# Mosfets.net
KiCad netlist of a schematic drawn in Altium Designer
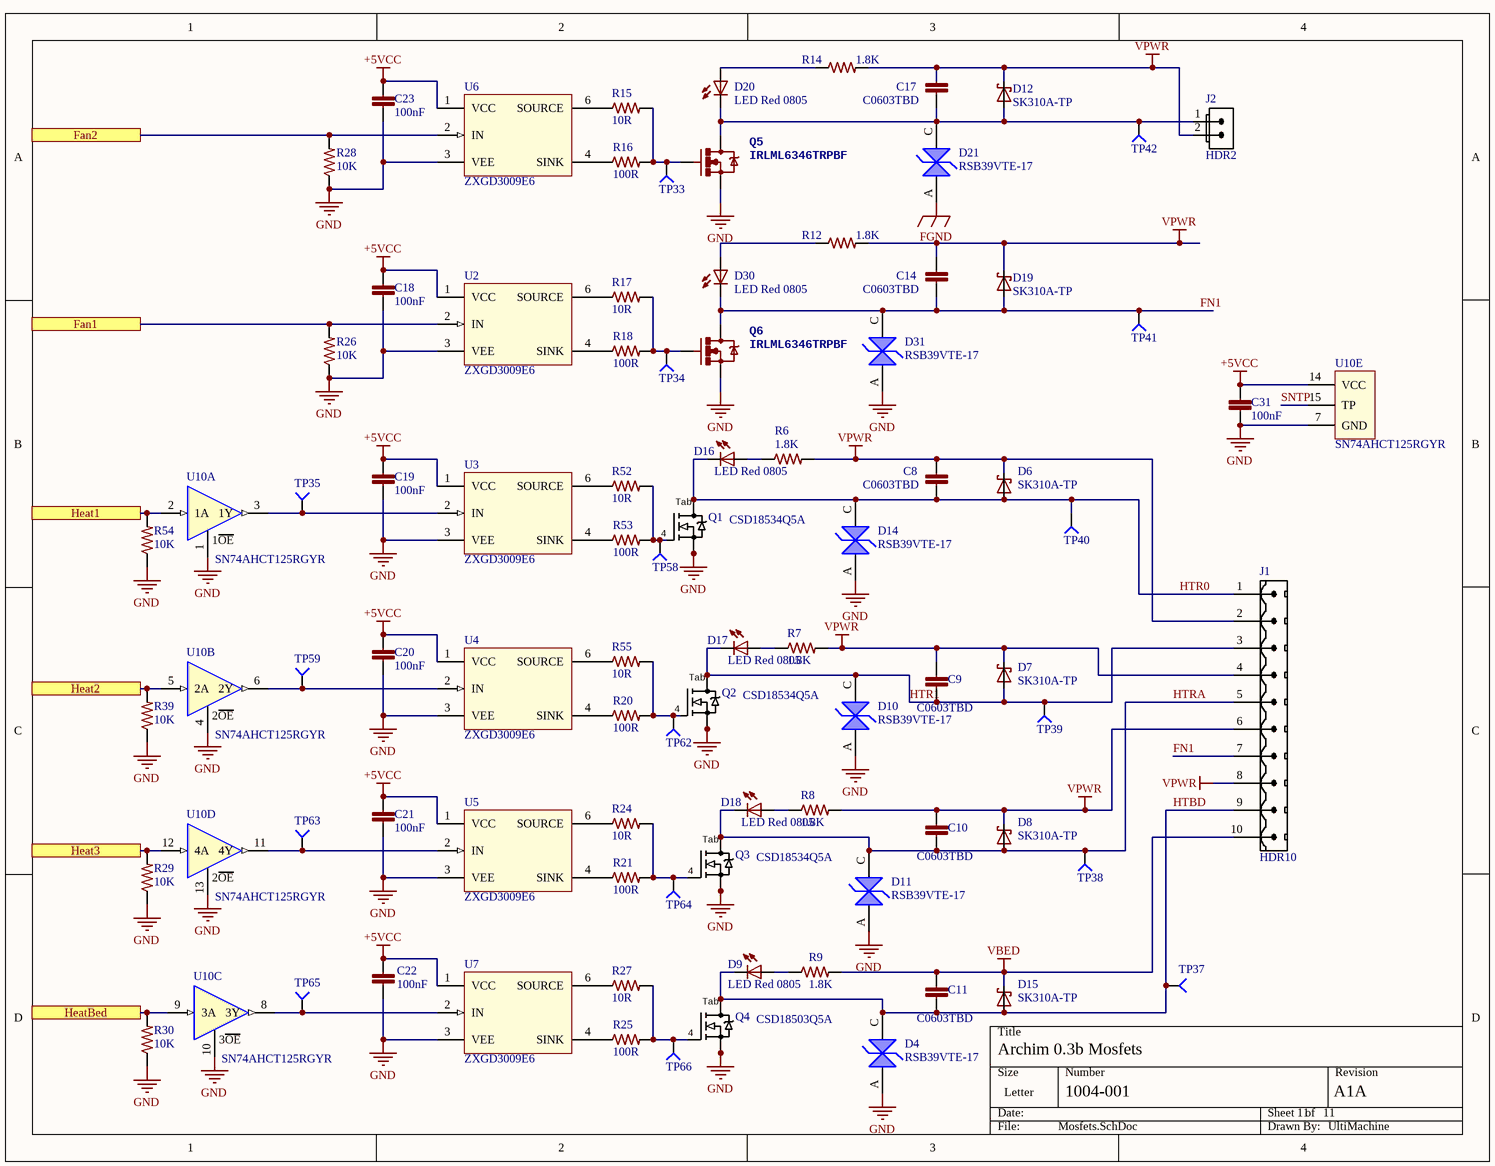
[diagram p0: Mosfets.SchDoc]

(export (version "E")
  (design (tool "Eeschema 10.0.6"))
  (components
    (comp (ref "C8")
      (value "C0603TBD")
      (footprint "C0603")
      (description "Capacitor Non Polarized")
      (libsource (lib "3Delight") (part "C0603TBD"))
    )
    (comp (ref "C9")
      (value "C0603TBD")
      (footprint "C0603")
      (description "Capacitor Non Polarized")
      (libsource (lib "3Delight") (part "C0603TBD"))
    )
    (comp (ref "C10")
      (value "C0603TBD")
      (footprint "C0603")
      (description "Capacitor Non Polarized")
      (libsource (lib "3Delight") (part "C0603TBD"))
    )
    (comp (ref "C11")
      (value "C0603TBD")
      (footprint "C0603")
      (description "Capacitor Non Polarized")
      (libsource (lib "3Delight") (part "C0603TBD"))
    )
    (comp (ref "C14")
      (value "C0603TBD")
      (footprint "C0603")
      (description "Capacitor Non Polarized")
      (libsource (lib "3Delight") (part "C0603TBD"))
    )
    (comp (ref "C17")
      (value "C0603TBD")
      (footprint "C0603")
      (description "Capacitor Non Polarized")
      (libsource (lib "3Delight") (part "C0603TBD"))
    )
    (comp (ref "C18")
      (value "100nF")
      (footprint "C0402")
      (description "CAP CER 0402 100nF 16V 10% X7R")
      (fields (field (name "MANUFACTURER") "Murata") (field (name "PART") "0.1uF 16V X7R 0402"))
      (libsource (lib "3Delight") (part "GRM155R71C104KA88D"))
    )
    (comp (ref "C19")
      (value "100nF")
      (footprint "C0402")
      (description "CAP CER 0402 100nF 16V 10% X7R")
      (fields (field (name "MANUFACTURER") "Murata") (field (name "PART") "0.1uF 16V X7R 0402"))
      (libsource (lib "3Delight") (part "GRM155R71C104KA88D"))
    )
    (comp (ref "C20")
      (value "100nF")
      (footprint "C0402")
      (description "CAP CER 0402 100nF 16V 10% X7R")
      (fields (field (name "MANUFACTURER") "Murata") (field (name "PART") "0.1uF 16V X7R 0402"))
      (libsource (lib "3Delight") (part "GRM155R71C104KA88D"))
    )
    (comp (ref "C21")
      (value "100nF")
      (footprint "C0402")
      (description "CAP CER 0402 100nF 16V 10% X7R")
      (fields (field (name "MANUFACTURER") "Murata") (field (name "PART") "0.1uF 16V X7R 0402"))
      (libsource (lib "3Delight") (part "GRM155R71C104KA88D"))
    )
    (comp (ref "C22")
      (value "100nF")
      (footprint "C0402")
      (description "CAP CER 0402 100nF 16V 10% X7R")
      (fields (field (name "MANUFACTURER") "Murata") (field (name "PART") "0.1uF 16V X7R 0402"))
      (libsource (lib "") (part "GRM155R71C104KA88D_1"))
    )
    (comp (ref "C23")
      (value "100nF")
      (footprint "C0402")
      (description "CAP CER 0402 100nF 16V 10% X7R")
      (fields (field (name "MANUFACTURER") "Murata") (field (name "PART") "0.1uF 16V X7R 0402"))
      (libsource (lib "3Delight") (part "GRM155R71C104KA88D"))
    )
    (comp (ref "C31")
      (value "100nF")
      (footprint "C0402")
      (description "CAP CER 0402 100nF 16V 10% X7R")
      (fields (field (name "MANUFACTURER") "Murata") (field (name "PART") "0.1uF 16V X7R 0402"))
      (libsource (lib "3Delight") (part "GRM155R71C104KA88D"))
    )
    (comp (ref "D4")
      (value "RSB39VTE-17")
      (footprint "SOD323-R")
      (description "DIODE TVS")
      (fields (field (name "MANUFACTURER") "Rohm") (field (name "PART") "TVS DIODE 30VWM SOD323"))
      (libsource (lib "3Delight") (part "RSB39VTE-17"))
    )
    (comp (ref "D6")
      (value "SK310A-TP")
      (footprint "SMA-SM")
      (description "DIODE Schottky 3A SMA")
      (fields (field (name "MANUFACTURER") "MCC") (field (name "PART") "Schottky Diode 100V 3A"))
      (libsource (lib "Archim_0.4") (part "SK310A"))
    )
    (comp (ref "D7")
      (value "SK310A-TP")
      (footprint "SMA-SM")
      (description "DIODE Schottky 3A SMA")
      (fields (field (name "MANUFACTURER") "MCC") (field (name "PART") "Schottky Diode 100V 3A"))
      (libsource (lib "Archim_0.4") (part "SK310A"))
    )
    (comp (ref "D8")
      (value "SK310A-TP")
      (footprint "SMA-SM")
      (description "DIODE Schottky 3A SMA")
      (fields (field (name "MANUFACTURER") "MCC") (field (name "PART") "Schottky Diode 100V 3A"))
      (libsource (lib "Archim_0.4") (part "SK310A"))
    )
    (comp (ref "D9")
      (value "Red")
      (footprint "LED2012120")
      (description "LED 0805 Red")
      (fields
        (field (name "MANUFACTURER") "Dialight")
        (field (name "PART") "LED Red 0805")
        (field (name "TOLERANCE") "-NA-")
      )
      (libsource (lib "3Delight") (part "5988110107F"))
    )
    (comp (ref "D10")
      (value "RSB39VTE-17")
      (footprint "SOD323-R")
      (description "DIODE TVS")
      (fields (field (name "MANUFACTURER") "Rohm") (field (name "PART") "TVS DIODE 30VWM SOD323"))
      (libsource (lib "3Delight") (part "RSB39VTE-17"))
    )
    (comp (ref "D11")
      (value "RSB39VTE-17")
      (footprint "SOD323-R")
      (description "DIODE TVS")
      (fields (field (name "MANUFACTURER") "Rohm") (field (name "PART") "TVS DIODE 30VWM SOD323"))
      (libsource (lib "3Delight") (part "RSB39VTE-17"))
    )
    (comp (ref "D12")
      (value "SK310A-TP")
      (footprint "SMA-SM")
      (description "DIODE Schottky 3A SMA")
      (fields (field (name "MANUFACTURER") "MCC") (field (name "PART") "Schottky Diode 100V 3A"))
      (libsource (lib "Archim_0.4") (part "SK310A"))
    )
    (comp (ref "D14")
      (value "RSB39VTE-17")
      (footprint "SOD323-R")
      (description "DIODE TVS")
      (fields (field (name "MANUFACTURER") "Rohm") (field (name "PART") "TVS DIODE 30VWM SOD323"))
      (libsource (lib "3Delight") (part "RSB39VTE-17"))
    )
    (comp (ref "D15")
      (value "SK310A-TP")
      (footprint "SMA-SM")
      (description "DIODE Schottky 3A SMA")
      (fields (field (name "MANUFACTURER") "MCC") (field (name "PART") "Schottky Diode 100V 3A"))
      (libsource (lib "Archim_0.4") (part "SK310A"))
    )
    (comp (ref "D16")
      (value "Red")
      (footprint "LED2012120")
      (description "LED 0805 Red")
      (fields
        (field (name "MANUFACTURER") "Dialight")
        (field (name "PART") "LED Red 0805")
        (field (name "TOLERANCE") "-NA-")
      )
      (libsource (lib "3Delight") (part "5988110107F"))
    )
    (comp (ref "D17")
      (value "Red")
      (footprint "LED2012120")
      (description "LED 0805 Red")
      (fields
        (field (name "MANUFACTURER") "Dialight")
        (field (name "PART") "LED Red 0805")
        (field (name "TOLERANCE") "-NA-")
      )
      (libsource (lib "3Delight") (part "5988110107F"))
    )
    (comp (ref "D18")
      (value "Red")
      (footprint "LED2012120")
      (description "LED 0805 Red")
      (fields
        (field (name "MANUFACTURER") "Dialight")
        (field (name "PART") "LED Red 0805")
        (field (name "TOLERANCE") "-NA-")
      )
      (libsource (lib "3Delight") (part "5988110107F"))
    )
    (comp (ref "D19")
      (value "SK310A-TP")
      (footprint "SMA-SM")
      (description "DIODE Schottky 3A SMA")
      (fields (field (name "MANUFACTURER") "MCC") (field (name "PART") "Schottky Diode 100V 3A"))
      (libsource (lib "Archim_0.4") (part "SK310A"))
    )
    (comp (ref "D20")
      (value "Red")
      (footprint "LED2012120")
      (description "LED 0805 Red")
      (fields
        (field (name "MANUFACTURER") "Dialight")
        (field (name "PART") "LED Red 0805")
        (field (name "TOLERANCE") "-NA-")
      )
      (libsource (lib "3Delight") (part "5988110107F"))
    )
    (comp (ref "D21")
      (value "RSB39VTE-17")
      (footprint "SOD323-R")
      (description "DIODE TVS")
      (fields (field (name "MANUFACTURER") "Rohm") (field (name "PART") "TVS DIODE 30VWM SOD323"))
      (libsource (lib "3Delight") (part "RSB39VTE-17"))
    )
    (comp (ref "D30")
      (value "Red")
      (footprint "LED2012120")
      (description "LED 0805 Red")
      (fields
        (field (name "MANUFACTURER") "Dialight")
        (field (name "PART") "LED Red 0805")
        (field (name "TOLERANCE") "-NA-")
      )
      (libsource (lib "3Delight") (part "5988110107F"))
    )
    (comp (ref "D31")
      (value "RSB39VTE-17")
      (footprint "SOD323-R")
      (description "DIODE TVS")
      (fields (field (name "MANUFACTURER") "Rohm") (field (name "PART") "TVS DIODE 30VWM SOD323"))
      (libsource (lib "3Delight") (part "RSB39VTE-17"))
    )
    (comp (ref "J1")
      (value "HDR10")
      (footprint "MSTBV10")
      (description "MSBTV10 10 port connector same as RAMBo")
      (fields
        (field (name "MANUFACTURER") "Molex")
        (field (name "PART") "CONN TERM BLOCK HDR 10POS VERT 5.08MM")
      )
      (libsource (lib "Archim_0.4") (part "CONN 10POS 0.2{dblquote} VERT SHRD"))
    )
    (comp (ref "J2")
      (value "HDR2")
      (footprint "70543-01 PIN-IN-PASTE")
      (description "Connector 2pos - Pin in Paste")
      (fields (field (name "MANUFACTURER") "Molex") (field (name "PART") "2 Pin Conn"))
      (libsource (lib "Connectors") (part "CONN 2PIN VERT 0.1{dblquote} SHRD LOCKING PIP"))
    )
    (comp (ref "Q1")
      (value "CSD18534Q5A")
      (footprint "SOT669_Universal")
      (description "MOSFET N-CH 40V 100A 8VSON")
      (fields (field (name "MANUFACTURER") "TI"))
      (libsource (lib "Transistors") (part "CSD18534Q5A"))
    )
    (comp (ref "Q2")
      (value "CSD18534Q5A")
      (footprint "SOT669_Universal")
      (description "MOSFET N-CH 40V 100A 8VSON")
      (fields (field (name "MANUFACTURER") "TI"))
      (libsource (lib "Transistors") (part "CSD18534Q5A"))
    )
    (comp (ref "Q3")
      (value "CSD18534Q5A")
      (footprint "SOT669_Universal")
      (description "MOSFET N-CH 40V 100A 8VSON")
      (fields (field (name "MANUFACTURER") "TI"))
      (libsource (lib "Transistors") (part "CSD18534Q5A"))
    )
    (comp (ref "Q4")
      (value "CSD18503Q5A")
      (footprint "SOT669_Universal")
      (description "MOSFET N-CH 40V 100A 8VSON")
      (fields (field (name "MANUFACTURER") "TI"))
      (libsource (lib "Transistors") (part "CSD18503Q5A"))
    )
    (comp (ref "Q5")
      (value "IRLML6346TRPBF")
      (footprint "SOT23-3")
      (description "Mosfet N-Channel 30V 3.4A 63mOhm")
      (fields (field (name "MANUFACTURER") "Infineon") (field (name "PART") "MOSFET N-Chan 30V 3.4A"))
      (libsource (lib "3Delight") (part "IRLML6346TRPBF"))
    )
    (comp (ref "Q6")
      (value "IRLML6346TRPBF")
      (footprint "SOT23-3")
      (description "Mosfet N-Channel 30V 3.4A 63mOhm")
      (fields (field (name "MANUFACTURER") "Infineon") (field (name "PART") "MOSFET N-Chan 30V 3.4A"))
      (libsource (lib "3Delight") (part "IRLML6346TRPBF"))
    )
    (comp (ref "R6")
      (value "1.8K")
      (footprint "R0603")
      (description "RES 0603 1.8K 100mW 5%")
      (fields (field (name "MANUFACTURER") "Yageo") (field (name "PART") "1.8k 5% 0603"))
      (libsource (lib "3Delight") (part "RC0603JR-071K8L"))
    )
    (comp (ref "R7")
      (value "1.8K")
      (footprint "R0603")
      (description "RES 0603 1.8K 100mW 5%")
      (fields (field (name "MANUFACTURER") "Yageo") (field (name "PART") "1.8k 5% 0603"))
      (libsource (lib "3Delight") (part "RC0603JR-071K8L"))
    )
    (comp (ref "R8")
      (value "1.8K")
      (footprint "R0603")
      (description "RES 0603 1.8K 100mW 5%")
      (fields (field (name "MANUFACTURER") "Yageo") (field (name "PART") "1.8k 5% 0603"))
      (libsource (lib "3Delight") (part "RC0603JR-071K8L"))
    )
    (comp (ref "R9")
      (value "1.8K")
      (footprint "R0603")
      (description "RES 0603 1.8K 100mW 5%")
      (fields (field (name "MANUFACTURER") "Yageo") (field (name "PART") "1.8k 5% 0603"))
      (libsource (lib "3Delight") (part "RC0603JR-071K8L"))
    )
    (comp (ref "R12")
      (value "1.8K")
      (footprint "R0603")
      (description "RES 0603 1.8K 100mW 5%")
      (fields (field (name "MANUFACTURER") "Yageo") (field (name "PART") "1.8k 5% 0603"))
      (libsource (lib "3Delight") (part "RC0603JR-071K8L"))
    )
    (comp (ref "R14")
      (value "1.8K")
      (footprint "R0603")
      (description "RES 0603 1.8K 100mW 5%")
      (fields (field (name "MANUFACTURER") "Yageo") (field (name "PART") "1.8k 5% 0603"))
      (libsource (lib "3Delight") (part "RC0603JR-071K8L"))
    )
    (comp (ref "R15")
      (value "10R")
      (footprint "R0402")
      (description "RES SMD 10 OHM 1% 1/16W 0402")
      (fields (field (name "MANUFACTURER") "Yageo") (field (name "TOLERANCE") "1%"))
      (libsource (lib "3Delight") (part "RC0402FR-0710RL"))
    )
    (comp (ref "R16")
      (value "100R")
      (footprint "R0402")
      (description "RES SMD 100 OHM 1% 1/16W 0402")
      (fields (field (name "MANUFACTURER") "Yageo") (field (name "PART") "100R 1% 0402"))
      (libsource (lib "Archim") (part "RES 100R 0402 1%"))
    )
    (comp (ref "R17")
      (value "10R")
      (footprint "R0402")
      (description "RES SMD 10 OHM 1% 1/16W 0402")
      (fields (field (name "MANUFACTURER") "Yageo") (field (name "TOLERANCE") "1%"))
      (libsource (lib "3Delight") (part "RC0402FR-0710RL"))
    )
    (comp (ref "R18")
      (value "100R")
      (footprint "R0402")
      (description "RES SMD 100 OHM 1% 1/16W 0402")
      (fields (field (name "MANUFACTURER") "Yageo") (field (name "PART") "100R 1% 0402"))
      (libsource (lib "Archim") (part "RES 100R 0402 1%"))
    )
    (comp (ref "R20")
      (value "100R")
      (footprint "R0402")
      (description "RES SMD 100 OHM 1% 1/16W 0402")
      (fields (field (name "MANUFACTURER") "Yageo") (field (name "PART") "100R 1% 0402"))
      (libsource (lib "Archim") (part "RES 100R 0402 1%"))
    )
    (comp (ref "R21")
      (value "100R")
      (footprint "R0402")
      (description "RES SMD 100 OHM 1% 1/16W 0402")
      (fields (field (name "MANUFACTURER") "Yageo") (field (name "PART") "100R 1% 0402"))
      (libsource (lib "Archim") (part "RES 100R 0402 1%"))
    )
    (comp (ref "R24")
      (value "10R")
      (footprint "R0402")
      (description "RES SMD 10 OHM 1% 1/16W 0402")
      (fields (field (name "MANUFACTURER") "Yageo") (field (name "TOLERANCE") "1%"))
      (libsource (lib "3Delight") (part "RC0402FR-0710RL"))
    )
    (comp (ref "R25")
      (value "100R")
      (footprint "R0402")
      (description "RES SMD 100 OHM 1% 1/16W 0402")
      (fields (field (name "MANUFACTURER") "Yageo") (field (name "PART") "100R 1% 0402"))
      (libsource (lib "Archim") (part "RES 100R 0402 1%"))
    )
    (comp (ref "R26")
      (value "10K")
      (footprint "R0402")
      (description "RES SMD 10K OHM 1% 1/16W 0402")
      (fields (field (name "MANUFACTURER") "Yageo") (field (name "PART") "10k 1% 0402"))
      (libsource (lib "3Delight") (part "RC0402FR-0710KP"))
    )
    (comp (ref "R27")
      (value "10R")
      (footprint "R0402")
      (description "RES SMD 10 OHM 1% 1/16W 0402")
      (fields (field (name "MANUFACTURER") "Yageo") (field (name "TOLERANCE") "1%"))
      (libsource (lib "3Delight") (part "RC0402FR-0710RL"))
    )
    (comp (ref "R28")
      (value "10K")
      (footprint "R0402")
      (description "RES SMD 10K OHM 1% 1/16W 0402")
      (fields (field (name "MANUFACTURER") "Yageo") (field (name "PART") "10k 1% 0402"))
      (libsource (lib "3Delight") (part "RC0402FR-0710KP"))
    )
    (comp (ref "R29")
      (value "10K")
      (footprint "R0402")
      (description "RES SMD 10K OHM 1% 1/16W 0402")
      (fields (field (name "MANUFACTURER") "Yageo") (field (name "PART") "10k 1% 0402"))
      (libsource (lib "3Delight") (part "RC0402FR-0710KP"))
    )
    (comp (ref "R30")
      (value "10K")
      (footprint "R0402")
      (description "RES SMD 10K OHM 1% 1/16W 0402")
      (fields (field (name "MANUFACTURER") "Yageo") (field (name "PART") "10k 1% 0402"))
      (libsource (lib "3Delight") (part "RC0402FR-0710KP"))
    )
    (comp (ref "R39")
      (value "10K")
      (footprint "R0402")
      (description "RES SMD 10K OHM 1% 1/16W 0402")
      (fields (field (name "MANUFACTURER") "Yageo") (field (name "PART") "10k 1% 0402"))
      (libsource (lib "3Delight") (part "RC0402FR-0710KP"))
    )
    (comp (ref "R52")
      (value "10R")
      (footprint "R0402")
      (description "RES SMD 10 OHM 1% 1/16W 0402")
      (fields (field (name "MANUFACTURER") "Yageo") (field (name "TOLERANCE") "1%"))
      (libsource (lib "3Delight") (part "RC0402FR-0710RL"))
    )
    (comp (ref "R53")
      (value "100R")
      (footprint "R0402")
      (description "RES SMD 100 OHM 1% 1/16W 0402")
      (fields (field (name "MANUFACTURER") "Yageo") (field (name "PART") "100R 1% 0402"))
      (libsource (lib "Archim") (part "RES 100R 0402 1%"))
    )
    (comp (ref "R54")
      (value "10K")
      (footprint "R0402")
      (description "RES SMD 10K OHM 1% 1/16W 0402")
      (fields (field (name "MANUFACTURER") "Yageo") (field (name "PART") "10k 1% 0402"))
      (libsource (lib "3Delight") (part "RC0402FR-0710KP"))
    )
    (comp (ref "R55")
      (value "10R")
      (footprint "R0402")
      (description "RES SMD 10 OHM 1% 1/16W 0402")
      (fields (field (name "MANUFACTURER") "Yageo") (field (name "TOLERANCE") "1%"))
      (libsource (lib "3Delight") (part "RC0402FR-0710RL"))
    )
    (comp (ref "TP33")
      (value "TP4")
      (footprint "TP-2")
      (description "Socket")
      (libsource (lib "Archim") (part "Socket"))
    )
    (comp (ref "TP34")
      (value "TP4")
      (footprint "TP-2")
      (description "Socket")
      (libsource (lib "Archim") (part "Socket"))
    )
    (comp (ref "TP35")
      (value "TP4")
      (footprint "TP-2")
      (description "Socket")
      (libsource (lib "Archim") (part "Socket"))
    )
    (comp (ref "TP37")
      (value "TP4")
      (footprint "TP-2")
      (description "Socket")
      (libsource (lib "Archim") (part "Socket"))
    )
    (comp (ref "TP38")
      (value "TP4")
      (footprint "TP-2")
      (description "Socket")
      (libsource (lib "Archim") (part "Socket"))
    )
    (comp (ref "TP39")
      (value "TP4")
      (footprint "TP-2")
      (description "Socket")
      (libsource (lib "Archim") (part "Socket"))
    )
    (comp (ref "TP40")
      (value "TP4")
      (footprint "TP-2")
      (description "Socket")
      (libsource (lib "Archim") (part "Socket"))
    )
    (comp (ref "TP41")
      (value "TP4")
      (footprint "TP-2")
      (description "Socket")
      (libsource (lib "Archim") (part "Socket"))
    )
    (comp (ref "TP42")
      (value "TP4")
      (footprint "TP-2")
      (description "Socket")
      (libsource (lib "Archim") (part "Socket"))
    )
    (comp (ref "TP58")
      (value "TP4")
      (footprint "TP-2")
      (description "Socket")
      (libsource (lib "Archim") (part "Socket"))
    )
    (comp (ref "TP59")
      (value "TP4")
      (footprint "TP-2")
      (description "Socket")
      (libsource (lib "Archim") (part "Socket"))
    )
    (comp (ref "TP62")
      (value "TP4")
      (footprint "TP-2")
      (description "Socket")
      (libsource (lib "Archim") (part "Socket"))
    )
    (comp (ref "TP63")
      (value "TP4")
      (footprint "TP-2")
      (description "Socket")
      (libsource (lib "Archim") (part "Socket"))
    )
    (comp (ref "TP64")
      (value "TP4")
      (footprint "TP-2")
      (description "Socket")
      (libsource (lib "Archim") (part "Socket"))
    )
    (comp (ref "TP65")
      (value "TP4")
      (footprint "TP-2")
      (description "Socket")
      (libsource (lib "Archim") (part "Socket"))
    )
    (comp (ref "TP66")
      (value "TP4")
      (footprint "TP-2")
      (description "Socket")
      (libsource (lib "Archim") (part "Socket"))
    )
    (comp (ref "U2")
      (value "ZXGD3009E6")
      (footprint "SOT26P285X140-6L")
      (description "MOSFET DRVR 3A 1-OUT High Speed Non-Inv6-Pin SOT-26 T/R")
      (fields
        (field (name "MANUFACTURER") "Diodes Incorporated")
        (field (name "PART") "IC GATE DRVR IGBT/MOSFET SOT23-6")
      )
      (libsource (lib "3Delight") (part "ZXGD3009E6"))
    )
    (comp (ref "U3")
      (value "ZXGD3009E6")
      (footprint "SOT26P285X140-6L")
      (description "MOSFET DRVR 3A 1-OUT High Speed Non-Inv6-Pin SOT-26 T/R")
      (fields
        (field (name "MANUFACTURER") "Diodes Incorporated")
        (field (name "PART") "IC GATE DRVR IGBT/MOSFET SOT23-6")
      )
      (libsource (lib "3Delight") (part "ZXGD3009E6"))
    )
    (comp (ref "U4")
      (value "ZXGD3009E6")
      (footprint "SOT26P285X140-6L")
      (description "MOSFET DRVR 3A 1-OUT High Speed Non-Inv6-Pin SOT-26 T/R")
      (fields
        (field (name "MANUFACTURER") "Diodes Incorporated")
        (field (name "PART") "IC GATE DRVR IGBT/MOSFET SOT23-6")
      )
      (libsource (lib "3Delight") (part "ZXGD3009E6"))
    )
    (comp (ref "U5")
      (value "ZXGD3009E6")
      (footprint "SOT26P285X140-6L")
      (description "MOSFET DRVR 3A 1-OUT High Speed Non-Inv6-Pin SOT-26 T/R")
      (fields
        (field (name "MANUFACTURER") "Diodes Incorporated")
        (field (name "PART") "IC GATE DRVR IGBT/MOSFET SOT23-6")
      )
      (libsource (lib "3Delight") (part "ZXGD3009E6"))
    )
    (comp (ref "U6")
      (value "ZXGD3009E6")
      (footprint "SOT26P285X140-6L")
      (description "MOSFET DRVR 3A 1-OUT High Speed Non-Inv6-Pin SOT-26 T/R")
      (fields
        (field (name "MANUFACTURER") "Diodes Incorporated")
        (field (name "PART") "IC GATE DRVR IGBT/MOSFET SOT23-6")
      )
      (libsource (lib "3Delight") (part "ZXGD3009E6"))
    )
    (comp (ref "U7")
      (value "ZXGD3009E6")
      (footprint "SOT26P285X140-6L")
      (description "MOSFET DRVR 3A 1-OUT High Speed Non-Inv6-Pin SOT-26 T/R")
      (fields
        (field (name "MANUFACTURER") "Diodes Incorporated")
        (field (name "PART") "IC GATE DRVR IGBT/MOSFET SOT23-6")
      )
      (libsource (lib "3Delight") (part "ZXGD3009E6"))
    )
    (comp (ref "U10")
      (value "SN74AHCT125RGYR")
      (footprint "QFN50P350X350X100_RGY_S-PVQFN-N14")
      (description "Quadruple Bus Buffer Gates With 3-State Outputs 14-VQFN -40 to 125")
      (fields
        (field (name "MANUFACTURER") "Texas Instruments")
        (field (name "PART") "IC BUS BUFFER TRI-ST QD 14VQFN")
      )
      (libsource (lib "3Delight") (part "SN74AHCT125"))
    )
  )
  (nets
    (net (code "1") (name "+5VCC") (class "Default")
      (node (ref "C18") (pin "2") (pinfunction "2_2") (pintype "passive"))
      (node (ref "C19") (pin "2") (pinfunction "2_2") (pintype "passive"))
      (node (ref "C20") (pin "2") (pinfunction "2_2") (pintype "passive"))
      (node (ref "C21") (pin "2") (pinfunction "2_2") (pintype "passive"))
      (node (ref "C22") (pin "1") (pinfunction "1_1") (pintype "passive"))
      (node (ref "C23") (pin "2") (pinfunction "2_2") (pintype "passive"))
      (node (ref "C31") (pin "2") (pinfunction "2_2") (pintype "passive"))
      (node (ref "U10") (pin "14") (pinfunction "VCC_14") (pintype "power_in"))
      (node (ref "U2") (pin "1") (pinfunction "VCC_1") (pintype "power_in"))
      (node (ref "U3") (pin "1") (pinfunction "VCC_1") (pintype "power_in"))
      (node (ref "U4") (pin "1") (pinfunction "VCC_1") (pintype "power_in"))
      (node (ref "U5") (pin "1") (pinfunction "VCC_1") (pintype "power_in"))
      (node (ref "U6") (pin "1") (pinfunction "VCC_1") (pintype "power_in"))
      (node (ref "U7") (pin "1") (pinfunction "VCC_1") (pintype "power_in"))
    )
    (net (code "2") (name "/FN1") (class "Default")
      (node (ref "C14") (pin "2") (pinfunction "2_2") (pintype "passive"))
      (node (ref "D19") (pin "A") (pinfunction "A_A") (pintype "passive"))
      (node (ref "D30") (pin "C") (pinfunction "C_C") (pintype "passive"))
      (node (ref "D31") (pin "C") (pinfunction "C_C") (pintype "power_in"))
      (node (ref "J1") (pin "7") (pinfunction "7_7") (pintype "passive"))
      (node (ref "Q6") (pin "3") (pinfunction "D_3") (pintype "passive"))
      (node (ref "TP41") (pin "1") (pinfunction "1_1") (pintype "passive"))
    )
    (net (code "3") (name "/Fan1") (class "Default")
      (node (ref "R26") (pin "2") (pinfunction "2_2") (pintype "passive"))
      (node (ref "U2") (pin "2") (pinfunction "IN_2") (pintype "input"))
    )
    (net (code "4") (name "/Fan2") (class "Default")
      (node (ref "R28") (pin "2") (pinfunction "2_2") (pintype "passive"))
      (node (ref "U6") (pin "2") (pinfunction "IN_2") (pintype "input"))
    )
    (net (code "5") (name "/HTBD") (class "Default")
      (node (ref "C11") (pin "2") (pinfunction "2_2") (pintype "passive"))
      (node (ref "D15") (pin "A") (pinfunction "A_A") (pintype "passive"))
      (node (ref "D4") (pin "C") (pinfunction "C_C") (pintype "power_in"))
      (node (ref "D9") (pin "C") (pinfunction "C_C") (pintype "passive"))
      (node (ref "J1") (pin "9") (pinfunction "9_9") (pintype "passive"))
      (node (ref "Q4") (pin "TAB") (pinfunction "D_TAB") (pintype "passive"))
      (node (ref "TP37") (pin "1") (pinfunction "1_1") (pintype "passive"))
    )
    (net (code "6") (name "/HTR0") (class "Default")
      (node (ref "C8") (pin "2") (pinfunction "2_2") (pintype "passive"))
      (node (ref "D14") (pin "C") (pinfunction "C_C") (pintype "power_in"))
      (node (ref "D16") (pin "C") (pinfunction "C_C") (pintype "passive"))
      (node (ref "D6") (pin "A") (pinfunction "A_A") (pintype "passive"))
      (node (ref "J1") (pin "1") (pinfunction "1_1") (pintype "passive"))
      (node (ref "Q1") (pin "TAB") (pinfunction "D_TAB") (pintype "passive"))
      (node (ref "TP40") (pin "1") (pinfunction "1_1") (pintype "passive"))
    )
    (net (code "7") (name "/HTR1") (class "Default")
      (node (ref "C9") (pin "2") (pinfunction "2_2") (pintype "passive"))
      (node (ref "D10") (pin "C") (pinfunction "C_C") (pintype "power_in"))
      (node (ref "D17") (pin "C") (pinfunction "C_C") (pintype "passive"))
      (node (ref "D7") (pin "A") (pinfunction "A_A") (pintype "passive"))
      (node (ref "J1") (pin "3") (pinfunction "3_3") (pintype "passive"))
      (node (ref "Q2") (pin "TAB") (pinfunction "D_TAB") (pintype "passive"))
      (node (ref "TP39") (pin "1") (pinfunction "1_1") (pintype "passive"))
    )
    (net (code "8") (name "/HTRA") (class "Default")
      (node (ref "C10") (pin "2") (pinfunction "2_2") (pintype "passive"))
      (node (ref "D11") (pin "C") (pinfunction "C_C") (pintype "power_in"))
      (node (ref "D18") (pin "C") (pinfunction "C_C") (pintype "passive"))
      (node (ref "D8") (pin "A") (pinfunction "A_A") (pintype "passive"))
      (node (ref "J1") (pin "5") (pinfunction "5_5") (pintype "passive"))
      (node (ref "Q3") (pin "TAB") (pinfunction "D_TAB") (pintype "passive"))
      (node (ref "TP38") (pin "1") (pinfunction "1_1") (pintype "passive"))
    )
    (net (code "9") (name "/Heat1") (class "Default")
      (node (ref "R54") (pin "2") (pinfunction "2_2") (pintype "passive"))
      (node (ref "U10") (pin "2") (pinfunction "1A_2") (pintype "input"))
    )
    (net (code "10") (name "/Heat2") (class "Default")
      (node (ref "R39") (pin "2") (pinfunction "2_2") (pintype "passive"))
      (node (ref "U10") (pin "5") (pinfunction "2A_5") (pintype "input"))
    )
    (net (code "11") (name "/Heat3") (class "Default")
      (node (ref "R29") (pin "2") (pinfunction "2_2") (pintype "passive"))
      (node (ref "U10") (pin "12") (pinfunction "4A_12") (pintype "input"))
    )
    (net (code "12") (name "/HeatBed") (class "Default")
      (node (ref "R30") (pin "2") (pinfunction "2_2") (pintype "passive"))
      (node (ref "U10") (pin "9") (pinfunction "3A_9") (pintype "input"))
    )
    (net (code "13") (name "/SNTP") (class "Default")
      (node (ref "U10") (pin "15") (pinfunction "TP_15") (pintype "power_in"))
    )
    (net (code "14") (name "FGND") (class "Default")
      (node (ref "D21") (pin "A") (pinfunction "A_A") (pintype "power_in"))
    )
    (net (code "15") (name "GND") (class "Default")
      (node (ref "C18") (pin "1") (pinfunction "1_1") (pintype "passive"))
      (node (ref "C19") (pin "1") (pinfunction "1_1") (pintype "passive"))
      (node (ref "C20") (pin "1") (pinfunction "1_1") (pintype "passive"))
      (node (ref "C21") (pin "1") (pinfunction "1_1") (pintype "passive"))
      (node (ref "C22") (pin "2") (pinfunction "2_2") (pintype "passive"))
      (node (ref "C23") (pin "1") (pinfunction "1_1") (pintype "passive"))
      (node (ref "C31") (pin "1") (pinfunction "1_1") (pintype "passive"))
      (node (ref "D10") (pin "A") (pinfunction "A_A") (pintype "power_in"))
      (node (ref "D11") (pin "A") (pinfunction "A_A") (pintype "power_in"))
      (node (ref "D14") (pin "A") (pinfunction "A_A") (pintype "power_in"))
      (node (ref "D31") (pin "A") (pinfunction "A_A") (pintype "power_in"))
      (node (ref "D4") (pin "A") (pinfunction "A_A") (pintype "power_in"))
      (node (ref "Q1") (pin "1") (pinfunction "S_1") (pintype "passive"))
      (node (ref "Q1") (pin "2") (pinfunction "S_2") (pintype "passive"))
      (node (ref "Q1") (pin "3") (pinfunction "S_3") (pintype "passive"))
      (node (ref "Q2") (pin "1") (pinfunction "S_1") (pintype "passive"))
      (node (ref "Q2") (pin "2") (pinfunction "S_2") (pintype "passive"))
      (node (ref "Q2") (pin "3") (pinfunction "S_3") (pintype "passive"))
      (node (ref "Q3") (pin "1") (pinfunction "S_1") (pintype "passive"))
      (node (ref "Q3") (pin "2") (pinfunction "S_2") (pintype "passive"))
      (node (ref "Q3") (pin "3") (pinfunction "S_3") (pintype "passive"))
      (node (ref "Q4") (pin "1") (pinfunction "S_1") (pintype "passive"))
      (node (ref "Q4") (pin "2") (pinfunction "S_2") (pintype "passive"))
      (node (ref "Q4") (pin "3") (pinfunction "S_3") (pintype "passive"))
      (node (ref "Q5") (pin "2") (pinfunction "S_2") (pintype "passive"))
      (node (ref "Q6") (pin "2") (pinfunction "S_2") (pintype "passive"))
      (node (ref "R26") (pin "1") (pinfunction "1_1") (pintype "passive"))
      (node (ref "R28") (pin "1") (pinfunction "1_1") (pintype "passive"))
      (node (ref "R29") (pin "1") (pinfunction "1_1") (pintype "passive"))
      (node (ref "R30") (pin "1") (pinfunction "1_1") (pintype "passive"))
      (node (ref "R39") (pin "1") (pinfunction "1_1") (pintype "passive"))
      (node (ref "R54") (pin "1") (pinfunction "1_1") (pintype "passive"))
      (node (ref "U10") (pin "1") (pinfunction "1OE_1") (pintype "power_in"))
      (node (ref "U10") (pin "10") (pinfunction "3OE_10") (pintype "power_in"))
      (node (ref "U10") (pin "13") (pinfunction "4OE_13") (pintype "power_in"))
      (node (ref "U10") (pin "4") (pinfunction "2OE_4") (pintype "power_in"))
      (node (ref "U10") (pin "7") (pinfunction "GND_7") (pintype "power_in"))
      (node (ref "U2") (pin "3") (pinfunction "VEE_3") (pintype "power_in"))
      (node (ref "U3") (pin "3") (pinfunction "VEE_3") (pintype "power_in"))
      (node (ref "U4") (pin "3") (pinfunction "VEE_3") (pintype "power_in"))
      (node (ref "U5") (pin "3") (pinfunction "VEE_3") (pintype "power_in"))
      (node (ref "U6") (pin "3") (pinfunction "VEE_3") (pintype "power_in"))
      (node (ref "U7") (pin "3") (pinfunction "VEE_3") (pintype "power_in"))
    )
    (net (code "16") (name "Net-(D9-PadA)") (class "Default")
      (node (ref "D9") (pin "A") (pinfunction "A_A") (pintype "passive"))
      (node (ref "R9") (pin "1") (pinfunction "1_1") (pintype "passive"))
    )
    (net (code "17") (name "Net-(D16-PadA)") (class "Default")
      (node (ref "D16") (pin "A") (pinfunction "A_A") (pintype "passive"))
      (node (ref "R6") (pin "1") (pinfunction "1_1") (pintype "passive"))
    )
    (net (code "18") (name "Net-(D17-PadA)") (class "Default")
      (node (ref "D17") (pin "A") (pinfunction "A_A") (pintype "passive"))
      (node (ref "R7") (pin "1") (pinfunction "1_1") (pintype "passive"))
    )
    (net (code "19") (name "Net-(D18-PadA)") (class "Default")
      (node (ref "D18") (pin "A") (pinfunction "A_A") (pintype "passive"))
      (node (ref "R8") (pin "1") (pinfunction "1_1") (pintype "passive"))
    )
    (net (code "20") (name "Net-(D20-PadA)") (class "Default")
      (node (ref "D20") (pin "A") (pinfunction "A_A") (pintype "passive"))
      (node (ref "R14") (pin "1") (pinfunction "1_1") (pintype "passive"))
    )
    (net (code "21") (name "Net-(D30-PadA)") (class "Default")
      (node (ref "D30") (pin "A") (pinfunction "A_A") (pintype "passive"))
      (node (ref "R12") (pin "1") (pinfunction "1_1") (pintype "passive"))
    )
    (net (code "22") (name "Net-(Q1-G)") (class "Default")
      (node (ref "Q1") (pin "4") (pinfunction "G_4") (pintype "passive"))
      (node (ref "R52") (pin "2") (pinfunction "2_2") (pintype "passive"))
      (node (ref "R53") (pin "2") (pinfunction "2_2") (pintype "passive"))
      (node (ref "TP58") (pin "1") (pinfunction "1_1") (pintype "passive"))
    )
    (net (code "23") (name "Net-(Q2-G)") (class "Default")
      (node (ref "Q2") (pin "4") (pinfunction "G_4") (pintype "passive"))
      (node (ref "R20") (pin "2") (pinfunction "2_2") (pintype "passive"))
      (node (ref "R55") (pin "2") (pinfunction "2_2") (pintype "passive"))
      (node (ref "TP62") (pin "1") (pinfunction "1_1") (pintype "passive"))
    )
    (net (code "24") (name "Net-(Q3-G)") (class "Default")
      (node (ref "Q3") (pin "4") (pinfunction "G_4") (pintype "passive"))
      (node (ref "R21") (pin "2") (pinfunction "2_2") (pintype "passive"))
      (node (ref "R24") (pin "2") (pinfunction "2_2") (pintype "passive"))
      (node (ref "TP64") (pin "1") (pinfunction "1_1") (pintype "passive"))
    )
    (net (code "25") (name "Net-(Q4-G)") (class "Default")
      (node (ref "Q4") (pin "4") (pinfunction "G_4") (pintype "passive"))
      (node (ref "R25") (pin "2") (pinfunction "2_2") (pintype "passive"))
      (node (ref "R27") (pin "2") (pinfunction "2_2") (pintype "passive"))
      (node (ref "TP66") (pin "1") (pinfunction "1_1") (pintype "passive"))
    )
    (net (code "26") (name "Net-(Q5-D)") (class "Default")
      (node (ref "C17") (pin "2") (pinfunction "2_2") (pintype "passive"))
      (node (ref "D12") (pin "A") (pinfunction "A_A") (pintype "passive"))
      (node (ref "D20") (pin "C") (pinfunction "C_C") (pintype "passive"))
      (node (ref "D21") (pin "C") (pinfunction "C_C") (pintype "power_in"))
      (node (ref "J2") (pin "1") (pinfunction "S_1") (pintype "passive"))
      (node (ref "Q5") (pin "3") (pinfunction "D_3") (pintype "passive"))
      (node (ref "TP42") (pin "1") (pinfunction "1_1") (pintype "passive"))
    )
    (net (code "27") (name "Net-(Q5-G)") (class "Default")
      (node (ref "Q5") (pin "1") (pinfunction "G_1") (pintype "passive"))
      (node (ref "R15") (pin "2") (pinfunction "2_2") (pintype "passive"))
      (node (ref "R16") (pin "2") (pinfunction "2_2") (pintype "passive"))
      (node (ref "TP33") (pin "1") (pinfunction "1_1") (pintype "passive"))
    )
    (net (code "28") (name "Net-(Q6-G)") (class "Default")
      (node (ref "Q6") (pin "1") (pinfunction "G_1") (pintype "passive"))
      (node (ref "R17") (pin "2") (pinfunction "2_2") (pintype "passive"))
      (node (ref "R18") (pin "2") (pinfunction "2_2") (pintype "passive"))
      (node (ref "TP34") (pin "1") (pinfunction "1_1") (pintype "passive"))
    )
    (net (code "29") (name "Net-(U2-SINK)") (class "Default")
      (node (ref "R18") (pin "1") (pinfunction "1_1") (pintype "passive"))
      (node (ref "U2") (pin "4") (pinfunction "SINK_4") (pintype "power_in"))
    )
    (net (code "30") (name "Net-(U2-SOURCE)") (class "Default")
      (node (ref "R17") (pin "1") (pinfunction "1_1") (pintype "passive"))
      (node (ref "U2") (pin "6") (pinfunction "SOURCE_6") (pintype "power_in"))
    )
    (net (code "31") (name "Net-(U3-SINK)") (class "Default")
      (node (ref "R53") (pin "1") (pinfunction "1_1") (pintype "passive"))
      (node (ref "U3") (pin "4") (pinfunction "SINK_4") (pintype "power_in"))
    )
    (net (code "32") (name "Net-(U3-SOURCE)") (class "Default")
      (node (ref "R52") (pin "1") (pinfunction "1_1") (pintype "passive"))
      (node (ref "U3") (pin "6") (pinfunction "SOURCE_6") (pintype "power_in"))
    )
    (net (code "33") (name "Net-(U4-SINK)") (class "Default")
      (node (ref "R20") (pin "1") (pinfunction "1_1") (pintype "passive"))
      (node (ref "U4") (pin "4") (pinfunction "SINK_4") (pintype "power_in"))
    )
    (net (code "34") (name "Net-(U4-SOURCE)") (class "Default")
      (node (ref "R55") (pin "1") (pinfunction "1_1") (pintype "passive"))
      (node (ref "U4") (pin "6") (pinfunction "SOURCE_6") (pintype "power_in"))
    )
    (net (code "35") (name "Net-(U5-SINK)") (class "Default")
      (node (ref "R21") (pin "1") (pinfunction "1_1") (pintype "passive"))
      (node (ref "U5") (pin "4") (pinfunction "SINK_4") (pintype "power_in"))
    )
    (net (code "36") (name "Net-(U5-SOURCE)") (class "Default")
      (node (ref "R24") (pin "1") (pinfunction "1_1") (pintype "passive"))
      (node (ref "U5") (pin "6") (pinfunction "SOURCE_6") (pintype "power_in"))
    )
    (net (code "37") (name "Net-(U6-SINK)") (class "Default")
      (node (ref "R16") (pin "1") (pinfunction "1_1") (pintype "passive"))
      (node (ref "U6") (pin "4") (pinfunction "SINK_4") (pintype "power_in"))
    )
    (net (code "38") (name "Net-(U6-SOURCE)") (class "Default")
      (node (ref "R15") (pin "1") (pinfunction "1_1") (pintype "passive"))
      (node (ref "U6") (pin "6") (pinfunction "SOURCE_6") (pintype "power_in"))
    )
    (net (code "39") (name "Net-(U7-SINK)") (class "Default")
      (node (ref "R25") (pin "1") (pinfunction "1_1") (pintype "passive"))
      (node (ref "U7") (pin "4") (pinfunction "SINK_4") (pintype "power_in"))
    )
    (net (code "40") (name "Net-(U7-SOURCE)") (class "Default")
      (node (ref "R27") (pin "1") (pinfunction "1_1") (pintype "passive"))
      (node (ref "U7") (pin "6") (pinfunction "SOURCE_6") (pintype "power_in"))
    )
    (net (code "41") (name "Net-(U10A-1Y)") (class "Default")
      (node (ref "TP35") (pin "1") (pinfunction "1_1") (pintype "passive"))
      (node (ref "U10") (pin "3") (pinfunction "1Y_3") (pintype "output"))
      (node (ref "U3") (pin "2") (pinfunction "IN_2") (pintype "input"))
    )
    (net (code "42") (name "Net-(U10B-2Y)") (class "Default")
      (node (ref "TP59") (pin "1") (pinfunction "1_1") (pintype "passive"))
      (node (ref "U10") (pin "6") (pinfunction "2Y_6") (pintype "output"))
      (node (ref "U4") (pin "2") (pinfunction "IN_2") (pintype "input"))
    )
    (net (code "43") (name "Net-(U10C-3Y)") (class "Default")
      (node (ref "TP65") (pin "1") (pinfunction "1_1") (pintype "passive"))
      (node (ref "U10") (pin "8") (pinfunction "3Y_8") (pintype "output"))
      (node (ref "U7") (pin "2") (pinfunction "IN_2") (pintype "input"))
    )
    (net (code "44") (name "Net-(U10D-4Y)") (class "Default")
      (node (ref "TP63") (pin "1") (pinfunction "1_1") (pintype "passive"))
      (node (ref "U10") (pin "11") (pinfunction "4Y_11") (pintype "output"))
      (node (ref "U5") (pin "2") (pinfunction "IN_2") (pintype "input"))
    )
    (net (code "45") (name "VBED") (class "Default")
      (node (ref "C11") (pin "1") (pinfunction "1_1") (pintype "passive"))
      (node (ref "D15") (pin "C") (pinfunction "C_C") (pintype "passive"))
      (node (ref "J1") (pin "10") (pinfunction "10_10") (pintype "passive"))
      (node (ref "R9") (pin "2") (pinfunction "2_2") (pintype "passive"))
    )
    (net (code "46") (name "VPWR") (class "Default")
      (node (ref "C10") (pin "1") (pinfunction "1_1") (pintype "passive"))
      (node (ref "C14") (pin "1") (pinfunction "1_1") (pintype "passive"))
      (node (ref "C17") (pin "1") (pinfunction "1_1") (pintype "passive"))
      (node (ref "C8") (pin "1") (pinfunction "1_1") (pintype "passive"))
      (node (ref "C9") (pin "1") (pinfunction "1_1") (pintype "passive"))
      (node (ref "D12") (pin "C") (pinfunction "C_C") (pintype "passive"))
      (node (ref "D19") (pin "C") (pinfunction "C_C") (pintype "passive"))
      (node (ref "D6") (pin "C") (pinfunction "C_C") (pintype "passive"))
      (node (ref "D7") (pin "C") (pinfunction "C_C") (pintype "passive"))
      (node (ref "D8") (pin "C") (pinfunction "C_C") (pintype "passive"))
      (node (ref "J1") (pin "2") (pinfunction "2_2") (pintype "passive"))
      (node (ref "J1") (pin "4") (pinfunction "4_4") (pintype "passive"))
      (node (ref "J1") (pin "6") (pinfunction "6_6") (pintype "passive"))
      (node (ref "J1") (pin "8") (pinfunction "8_8") (pintype "passive"))
      (node (ref "J2") (pin "2") (pinfunction "S_2") (pintype "passive"))
      (node (ref "R12") (pin "2") (pinfunction "2_2") (pintype "passive"))
      (node (ref "R14") (pin "2") (pinfunction "2_2") (pintype "passive"))
      (node (ref "R6") (pin "2") (pinfunction "2_2") (pintype "passive"))
      (node (ref "R7") (pin "2") (pinfunction "2_2") (pintype "passive"))
      (node (ref "R8") (pin "2") (pinfunction "2_2") (pintype "passive"))
    )
  )
)
